# 6ch-dimmer.net
KiCad netlist of a schematic drawn in EAGLE
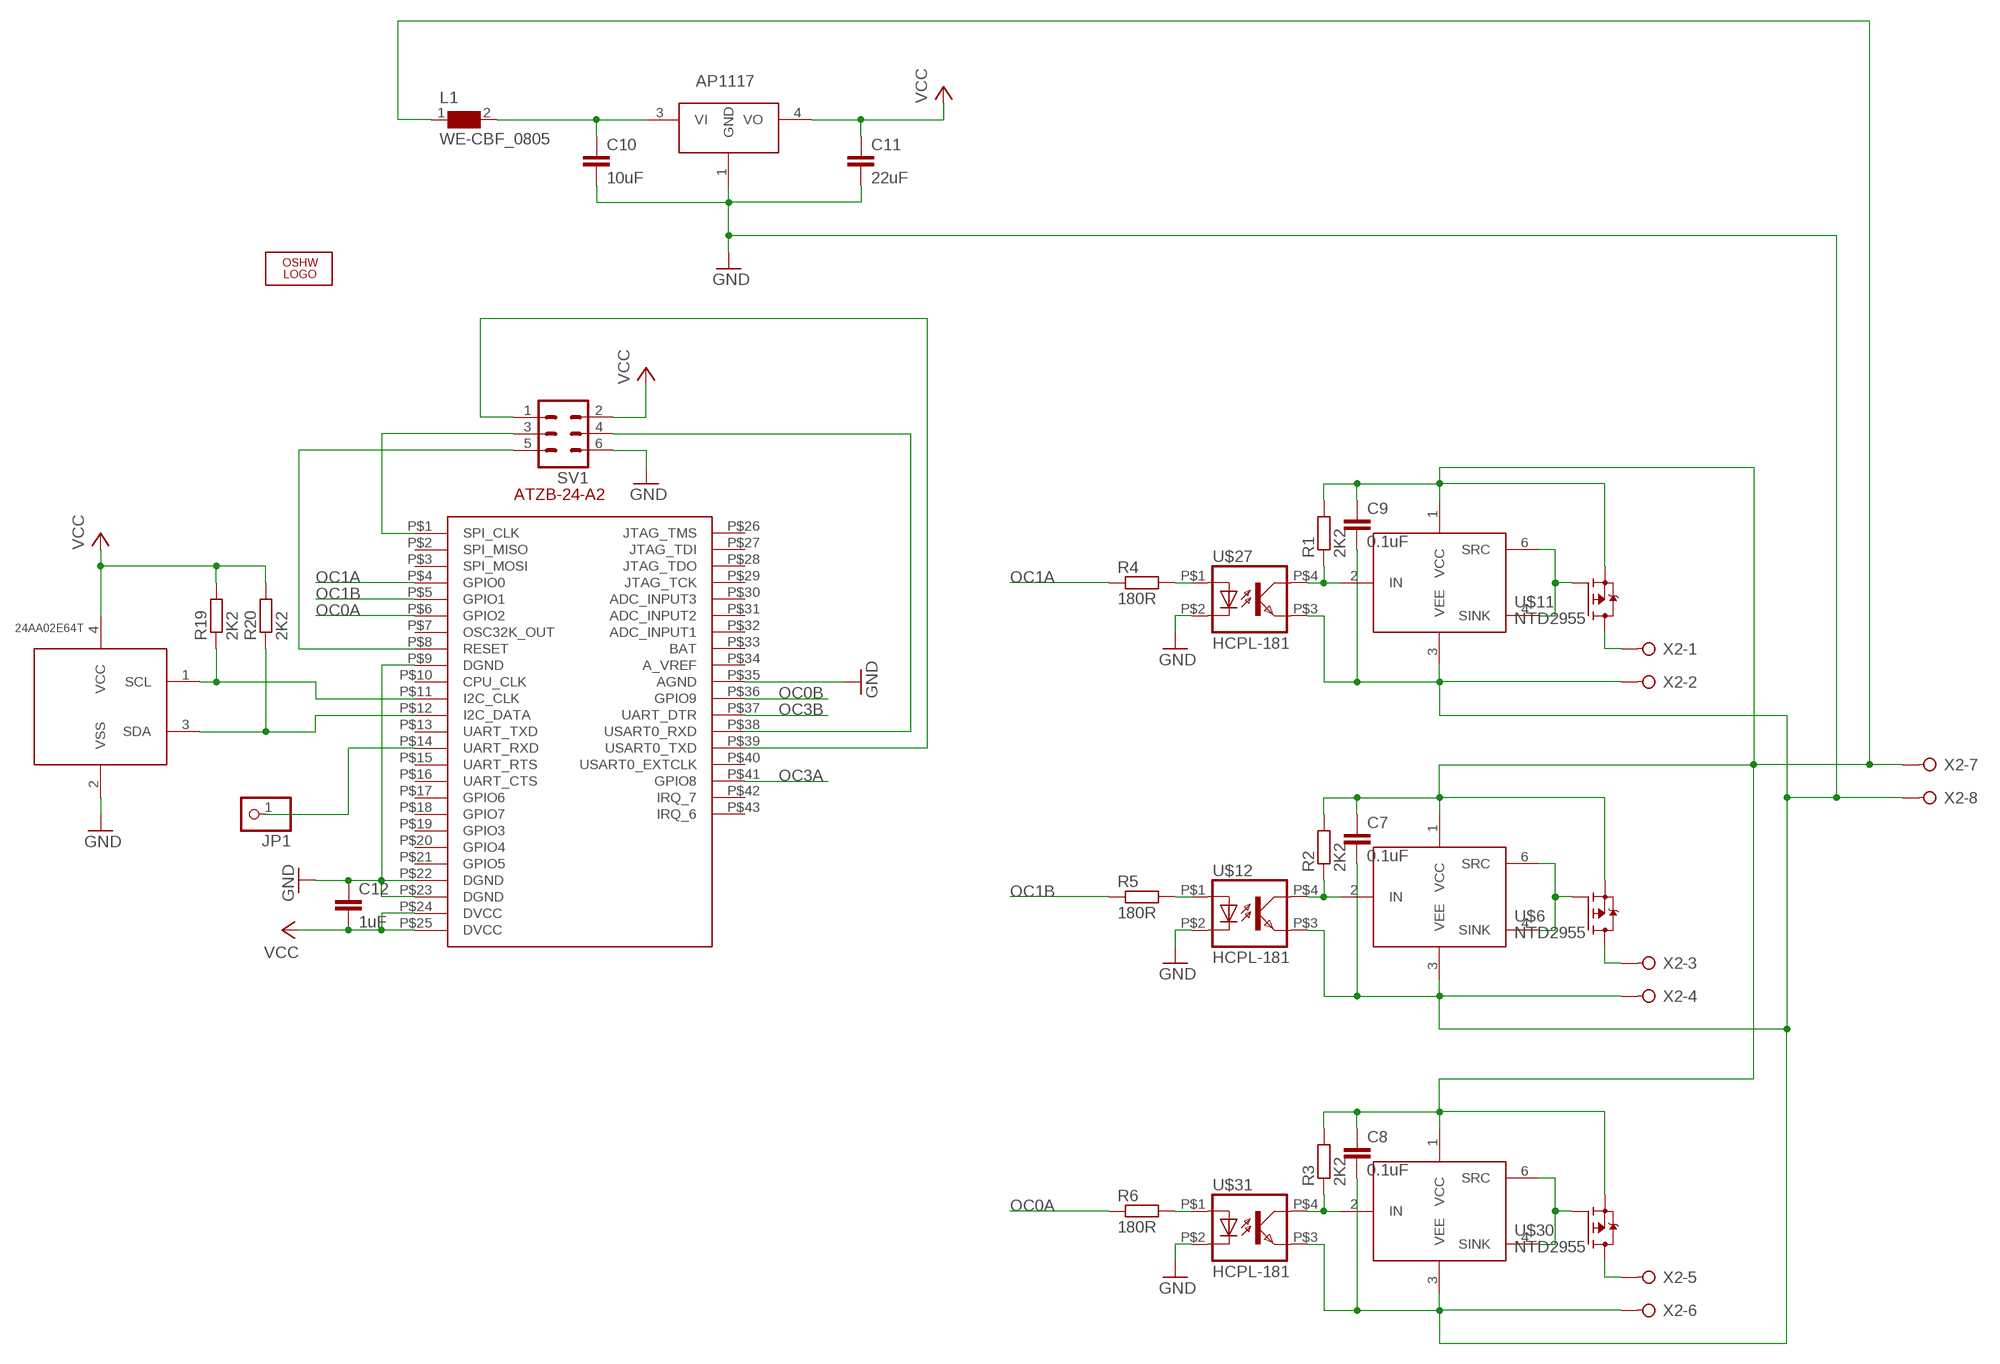
[diagram p0: schematic, sheet 1, part 1 of 2]
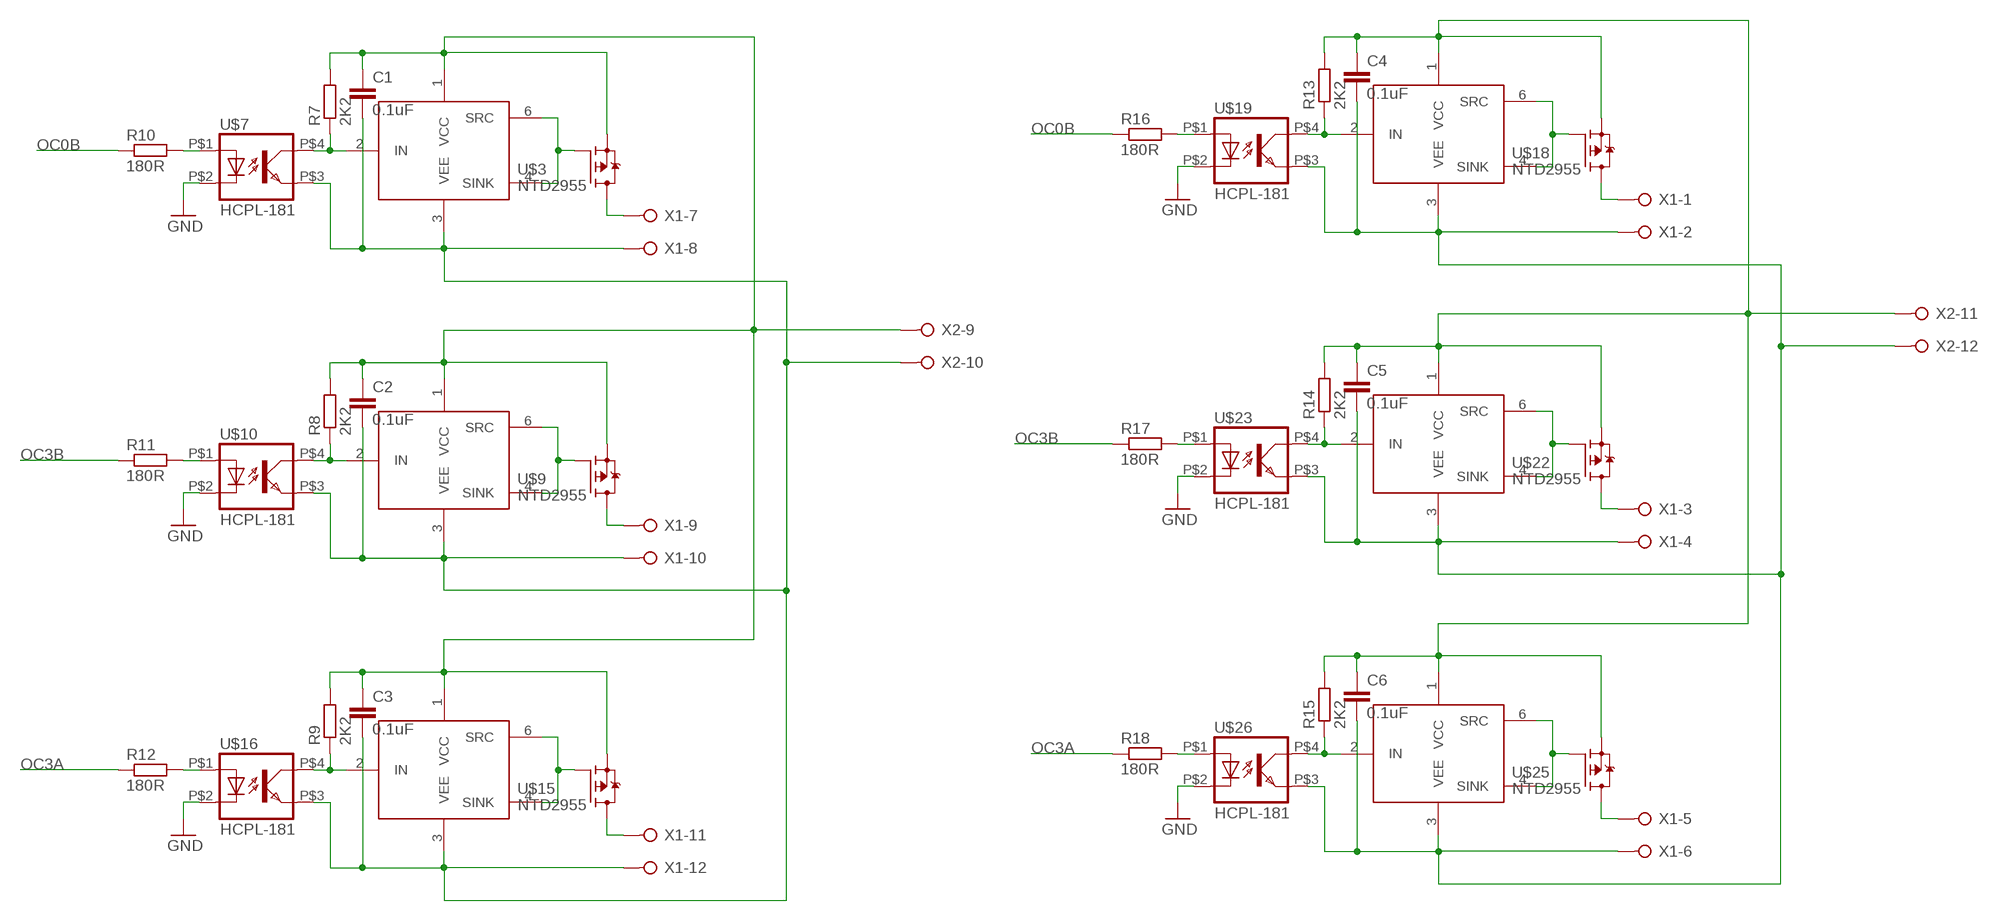
[diagram p1: schematic, sheet 1, part 2 of 2]

(export (version "E")
  (design (tool "Eeschema 10.0.6"))
  (components
    (comp (ref "C1")
      (value "0.1uF")
      (footprint "eagle-import:C0603")
      (libsource (lib "eagle-import") (part "C-EUC0603"))
    )
    (comp (ref "C2")
      (value "0.1uF")
      (footprint "eagle-import:C0603")
      (libsource (lib "eagle-import") (part "C-EUC0603"))
    )
    (comp (ref "C3")
      (value "0.1uF")
      (footprint "eagle-import:C0603")
      (libsource (lib "eagle-import") (part "C-EUC0603"))
    )
    (comp (ref "C4")
      (value "0.1uF")
      (footprint "eagle-import:C0603")
      (libsource (lib "eagle-import") (part "C-EUC0603"))
    )
    (comp (ref "C5")
      (value "0.1uF")
      (footprint "eagle-import:C0603")
      (libsource (lib "eagle-import") (part "C-EUC0603"))
    )
    (comp (ref "C6")
      (value "0.1uF")
      (footprint "eagle-import:C0603")
      (libsource (lib "eagle-import") (part "C-EUC0603"))
    )
    (comp (ref "C7")
      (value "0.1uF")
      (footprint "eagle-import:C0603")
      (libsource (lib "eagle-import") (part "C-EUC0603"))
    )
    (comp (ref "C8")
      (value "0.1uF")
      (footprint "eagle-import:C0603")
      (libsource (lib "eagle-import") (part "C-EUC0603"))
    )
    (comp (ref "C9")
      (value "0.1uF")
      (footprint "eagle-import:C0603")
      (libsource (lib "eagle-import") (part "C-EUC0603"))
    )
    (comp (ref "C10")
      (value "10uF")
      (footprint "eagle-import:C1210")
      (libsource (lib "eagle-import") (part "C-EUC1210"))
    )
    (comp (ref "C11")
      (value "22uF")
      (footprint "eagle-import:C1210")
      (libsource (lib "eagle-import") (part "C-EUC1210"))
    )
    (comp (ref "C12")
      (value "1uF")
      (footprint "eagle-import:C0603")
      (libsource (lib "eagle-import") (part "C-EUC0603"))
    )
    (comp (ref "JP1")
      (value "PINHD-1X1")
      (footprint "eagle-import:1X01")
      (libsource (lib "eagle-import") (part "PINHD-1X1"))
    )
    (comp (ref "L1")
      (value "WE-CBF_0805")
      (footprint "eagle-import:0805")
      (libsource (lib "eagle-import") (part "WE-CBF_0805"))
    )
    (comp (ref "LOGO1")
      (value "OSHW_LOGO_10MILX0500-NT")
      (footprint "eagle-import:OSHW_10X500_NOTEXT")
      (libsource (lib "eagle-import") (part "OSHW_LOGO_10MILX0500-NT"))
    )
    (comp (ref "R1")
      (value "2K2")
      (footprint "eagle-import:R0603")
      (libsource (lib "eagle-import") (part "R-EU_R0603"))
    )
    (comp (ref "R2")
      (value "2K2")
      (footprint "eagle-import:R0603")
      (libsource (lib "eagle-import") (part "R-EU_R0603"))
    )
    (comp (ref "R3")
      (value "2K2")
      (footprint "eagle-import:R0603")
      (libsource (lib "eagle-import") (part "R-EU_R0603"))
    )
    (comp (ref "R4")
      (value "180R")
      (footprint "eagle-import:R0603")
      (libsource (lib "eagle-import") (part "R-EU_R0603"))
    )
    (comp (ref "R5")
      (value "180R")
      (footprint "eagle-import:R0603")
      (libsource (lib "eagle-import") (part "R-EU_R0603"))
    )
    (comp (ref "R6")
      (value "180R")
      (footprint "eagle-import:R0603")
      (libsource (lib "eagle-import") (part "R-EU_R0603"))
    )
    (comp (ref "R7")
      (value "2K2")
      (footprint "eagle-import:R0603")
      (libsource (lib "eagle-import") (part "R-EU_R0603"))
    )
    (comp (ref "R8")
      (value "2K2")
      (footprint "eagle-import:R0603")
      (libsource (lib "eagle-import") (part "R-EU_R0603"))
    )
    (comp (ref "R9")
      (value "2K2")
      (footprint "eagle-import:R0603")
      (libsource (lib "eagle-import") (part "R-EU_R0603"))
    )
    (comp (ref "R10")
      (value "180R")
      (footprint "eagle-import:R0603")
      (libsource (lib "eagle-import") (part "R-EU_R0603"))
    )
    (comp (ref "R11")
      (value "180R")
      (footprint "eagle-import:R0603")
      (libsource (lib "eagle-import") (part "R-EU_R0603"))
    )
    (comp (ref "R12")
      (value "180R")
      (footprint "eagle-import:R0603")
      (libsource (lib "eagle-import") (part "R-EU_R0603"))
    )
    (comp (ref "R13")
      (value "2K2")
      (footprint "eagle-import:R0603")
      (libsource (lib "eagle-import") (part "R-EU_R0603"))
    )
    (comp (ref "R14")
      (value "2K2")
      (footprint "eagle-import:R0603")
      (libsource (lib "eagle-import") (part "R-EU_R0603"))
    )
    (comp (ref "R15")
      (value "2K2")
      (footprint "eagle-import:R0603")
      (libsource (lib "eagle-import") (part "R-EU_R0603"))
    )
    (comp (ref "R16")
      (value "180R")
      (footprint "eagle-import:R0603")
      (libsource (lib "eagle-import") (part "R-EU_R0603"))
    )
    (comp (ref "R17")
      (value "180R")
      (footprint "eagle-import:R0603")
      (libsource (lib "eagle-import") (part "R-EU_R0603"))
    )
    (comp (ref "R18")
      (value "180R")
      (footprint "eagle-import:R0603")
      (libsource (lib "eagle-import") (part "R-EU_R0603"))
    )
    (comp (ref "R19")
      (value "2K2")
      (footprint "eagle-import:R0603")
      (libsource (lib "eagle-import") (part "R-EU_R0603"))
    )
    (comp (ref "R20")
      (value "2K2")
      (footprint "eagle-import:R0603")
      (libsource (lib "eagle-import") (part "R-EU_R0603"))
    )
    (comp (ref "SV1")
      (value "MA03-2")
      (footprint "eagle-import:MA03-2")
      (libsource (lib "eagle-import") (part "MA03-2"))
    )
    (comp (ref "U$1")
      (value "ATZB-24-A2")
      (footprint "eagle-import:ATZB-24-A2")
      (libsource (lib "eagle-import") (part "ATZB-24-A2"))
    )
    (comp (ref "U$2")
      (value "ZXGD3005E6")
      (footprint "eagle-import:SOT23-6")
      (libsource (lib "eagle-import") (part "ZXGD3005E6"))
    )
    (comp (ref "U$3")
      (value "NTD2955")
      (footprint "eagle-import:DPAK")
      (libsource (lib "eagle-import") (part "NTD2955"))
    )
    (comp (ref "U$4")
      (value "ZXGD3005E6")
      (footprint "eagle-import:SOT23-6")
      (libsource (lib "eagle-import") (part "ZXGD3005E6"))
    )
    (comp (ref "U$5")
      (value "ZXGD3005E6")
      (footprint "eagle-import:SOT23-6")
      (libsource (lib "eagle-import") (part "ZXGD3005E6"))
    )
    (comp (ref "U$6")
      (value "NTD2955")
      (footprint "eagle-import:DPAK")
      (libsource (lib "eagle-import") (part "NTD2955"))
    )
    (comp (ref "U$7")
      (value "HCPL-181")
      (footprint "eagle-import:HCPL-181")
      (libsource (lib "eagle-import") (part "HCPL-181"))
    )
    (comp (ref "U$8")
      (value "ZXGD3005E6")
      (footprint "eagle-import:SOT23-6")
      (libsource (lib "eagle-import") (part "ZXGD3005E6"))
    )
    (comp (ref "U$9")
      (value "NTD2955")
      (footprint "eagle-import:DPAK")
      (libsource (lib "eagle-import") (part "NTD2955"))
    )
    (comp (ref "U$10")
      (value "HCPL-181")
      (footprint "eagle-import:HCPL-181")
      (libsource (lib "eagle-import") (part "HCPL-181"))
    )
    (comp (ref "U$11")
      (value "NTD2955")
      (footprint "eagle-import:DPAK")
      (libsource (lib "eagle-import") (part "NTD2955"))
    )
    (comp (ref "U$12")
      (value "HCPL-181")
      (footprint "eagle-import:HCPL-181")
      (libsource (lib "eagle-import") (part "HCPL-181"))
    )
    (comp (ref "U$13")
      (value "ZXGD3005E6")
      (footprint "eagle-import:SOT23-6")
      (libsource (lib "eagle-import") (part "ZXGD3005E6"))
    )
    (comp (ref "U$14")
      (value "ZXGD3005E6")
      (footprint "eagle-import:SOT23-6")
      (libsource (lib "eagle-import") (part "ZXGD3005E6"))
    )
    (comp (ref "U$15")
      (value "NTD2955")
      (footprint "eagle-import:DPAK")
      (libsource (lib "eagle-import") (part "NTD2955"))
    )
    (comp (ref "U$16")
      (value "HCPL-181")
      (footprint "eagle-import:HCPL-181")
      (libsource (lib "eagle-import") (part "HCPL-181"))
    )
    (comp (ref "U$17")
      (value "ZXGD3005E6")
      (footprint "eagle-import:SOT23-6")
      (libsource (lib "eagle-import") (part "ZXGD3005E6"))
    )
    (comp (ref "U$18")
      (value "NTD2955")
      (footprint "eagle-import:DPAK")
      (libsource (lib "eagle-import") (part "NTD2955"))
    )
    (comp (ref "U$19")
      (value "HCPL-181")
      (footprint "eagle-import:HCPL-181")
      (libsource (lib "eagle-import") (part "HCPL-181"))
    )
    (comp (ref "U$20")
      (value "24AA02E64T")
      (footprint "eagle-import:SOT23-5L")
      (libsource (lib "eagle-import") (part "24AA02E64T"))
    )
    (comp (ref "U$21")
      (value "ZXGD3005E6")
      (footprint "eagle-import:SOT23-6")
      (libsource (lib "eagle-import") (part "ZXGD3005E6"))
    )
    (comp (ref "U$22")
      (value "NTD2955")
      (footprint "eagle-import:DPAK")
      (libsource (lib "eagle-import") (part "NTD2955"))
    )
    (comp (ref "U$23")
      (value "HCPL-181")
      (footprint "eagle-import:HCPL-181")
      (libsource (lib "eagle-import") (part "HCPL-181"))
    )
    (comp (ref "U$24")
      (value "ZXGD3005E6")
      (footprint "eagle-import:SOT23-6")
      (libsource (lib "eagle-import") (part "ZXGD3005E6"))
    )
    (comp (ref "U$25")
      (value "NTD2955")
      (footprint "eagle-import:DPAK")
      (libsource (lib "eagle-import") (part "NTD2955"))
    )
    (comp (ref "U$26")
      (value "HCPL-181")
      (footprint "eagle-import:HCPL-181")
      (libsource (lib "eagle-import") (part "HCPL-181"))
    )
    (comp (ref "U$27")
      (value "HCPL-181")
      (footprint "eagle-import:HCPL-181")
      (libsource (lib "eagle-import") (part "HCPL-181"))
    )
    (comp (ref "U$28")
      (value "AP1117")
      (footprint "eagle-import:SOT223")
      (libsource (lib "eagle-import") (part "AP1117"))
    )
    (comp (ref "U$30")
      (value "NTD2955")
      (footprint "eagle-import:DPAK")
      (libsource (lib "eagle-import") (part "NTD2955"))
    )
    (comp (ref "U$31")
      (value "HCPL-181")
      (footprint "eagle-import:HCPL-181")
      (libsource (lib "eagle-import") (part "HCPL-181"))
    )
    (comp (ref "X1")
      (value "W237-12P")
      (footprint "eagle-import:W237-12P")
      (libsource (lib "eagle-import") (part "W237-12P"))
    )
    (comp (ref "X2")
      (value "W237-12P")
      (footprint "eagle-import:W237-12P")
      (libsource (lib "eagle-import") (part "W237-12P"))
    )
  )
  (nets
    (net (code "1") (name "/OC0A") (class "Default")
      (node (ref "R6") (pin "1") (pinfunction "1_1") (pintype "passive"))
      (node (ref "U$1") (pin "P$6") (pinfunction "GPIO2_P$6") (pintype "bidirectional"))
    )
    (net (code "2") (name "/OC0B") (class "Default")
      (node (ref "R10") (pin "1") (pinfunction "1_1") (pintype "passive"))
      (node (ref "R16") (pin "1") (pinfunction "1_1") (pintype "passive"))
      (node (ref "U$1") (pin "P$36") (pinfunction "GPIO9_P$36") (pintype "bidirectional"))
    )
    (net (code "3") (name "/OC1A") (class "Default")
      (node (ref "R4") (pin "1") (pinfunction "1_1") (pintype "passive"))
      (node (ref "U$1") (pin "P$4") (pinfunction "GPIO0_P$4") (pintype "bidirectional"))
    )
    (net (code "4") (name "/OC1B") (class "Default")
      (node (ref "R5") (pin "1") (pinfunction "1_1") (pintype "passive"))
      (node (ref "U$1") (pin "P$5") (pinfunction "GPIO1_P$5") (pintype "bidirectional"))
    )
    (net (code "5") (name "/OC3A") (class "Default")
      (node (ref "R12") (pin "1") (pinfunction "1_1") (pintype "passive"))
      (node (ref "R18") (pin "1") (pinfunction "1_1") (pintype "passive"))
      (node (ref "U$1") (pin "P$41") (pinfunction "GPIO8_P$41") (pintype "bidirectional"))
    )
    (net (code "6") (name "/OC3B") (class "Default")
      (node (ref "R11") (pin "1") (pinfunction "1_1") (pintype "passive"))
      (node (ref "R17") (pin "1") (pinfunction "1_1") (pintype "passive"))
      (node (ref "U$1") (pin "P$37") (pinfunction "UART_DTR_P$37") (pintype "bidirectional"))
    )
    (net (code "7") (name "GND") (class "Default")
      (node (ref "C10") (pin "2") (pinfunction "2_2") (pintype "passive"))
      (node (ref "C11") (pin "2") (pinfunction "2_2") (pintype "passive"))
      (node (ref "C12") (pin "1") (pinfunction "1_1") (pintype "passive"))
      (node (ref "C7") (pin "2") (pinfunction "2_2") (pintype "passive"))
      (node (ref "C8") (pin "2") (pinfunction "2_2") (pintype "passive"))
      (node (ref "C9") (pin "2") (pinfunction "2_2") (pintype "passive"))
      (node (ref "SV1") (pin "6") (pinfunction "6_6") (pintype "passive"))
      (node (ref "U$1") (pin "P$22") (pinfunction "DGND_P$22") (pintype "bidirectional"))
      (node (ref "U$1") (pin "P$23") (pinfunction "DGND_P$23") (pintype "bidirectional"))
      (node (ref "U$1") (pin "P$35") (pinfunction "AGND_P$35") (pintype "bidirectional"))
      (node (ref "U$1") (pin "P$9") (pinfunction "DGND_P$9") (pintype "bidirectional"))
      (node (ref "U$10") (pin "P$2") (pinfunction "C_P$2") (pintype "passive"))
      (node (ref "U$12") (pin "P$2") (pinfunction "C_P$2") (pintype "passive"))
      (node (ref "U$12") (pin "P$3") (pinfunction "EMIT_P$3") (pintype "passive"))
      (node (ref "U$13") (pin "3") (pinfunction "VEE_3") (pintype "bidirectional"))
      (node (ref "U$16") (pin "P$2") (pinfunction "C_P$2") (pintype "passive"))
      (node (ref "U$19") (pin "P$2") (pinfunction "C_P$2") (pintype "passive"))
      (node (ref "U$20") (pin "2") (pinfunction "VSS_2") (pintype "bidirectional"))
      (node (ref "U$23") (pin "P$2") (pinfunction "C_P$2") (pintype "passive"))
      (node (ref "U$26") (pin "P$2") (pinfunction "C_P$2") (pintype "passive"))
      (node (ref "U$27") (pin "P$2") (pinfunction "C_P$2") (pintype "passive"))
      (node (ref "U$27") (pin "P$3") (pinfunction "EMIT_P$3") (pintype "passive"))
      (node (ref "U$28") (pin "1") (pinfunction "GND_1") (pintype "bidirectional"))
      (node (ref "U$31") (pin "P$2") (pinfunction "C_P$2") (pintype "passive"))
      (node (ref "U$31") (pin "P$3") (pinfunction "EMIT_P$3") (pintype "passive"))
      (node (ref "U$4") (pin "3") (pinfunction "VEE_3") (pintype "bidirectional"))
      (node (ref "U$5") (pin "3") (pinfunction "VEE_3") (pintype "bidirectional"))
      (node (ref "U$7") (pin "P$2") (pinfunction "C_P$2") (pintype "passive"))
      (node (ref "X2") (pin "2") (pinfunction "KL_2") (pintype "passive"))
      (node (ref "X2") (pin "4") (pinfunction "KL_4") (pintype "passive"))
      (node (ref "X2") (pin "6") (pinfunction "KL_6") (pintype "passive"))
      (node (ref "X2") (pin "8") (pinfunction "KL_8") (pintype "passive"))
    )
    (net (code "8") (name "Net-(U$1-I2C_CLK)") (class "Default")
      (node (ref "R19") (pin "1") (pinfunction "1_1") (pintype "passive"))
      (node (ref "U$1") (pin "P$11") (pinfunction "I2C_CLK_P$11") (pintype "bidirectional"))
      (node (ref "U$20") (pin "1") (pinfunction "SCL_1") (pintype "bidirectional"))
    )
    (net (code "9") (name "Net-(U$1-I2C_DATA)") (class "Default")
      (node (ref "R20") (pin "1") (pinfunction "1_1") (pintype "passive"))
      (node (ref "U$1") (pin "P$12") (pinfunction "I2C_DATA_P$12") (pintype "bidirectional"))
      (node (ref "U$20") (pin "3") (pinfunction "SDA_3") (pintype "bidirectional"))
    )
    (net (code "10") (name "Net-(U$1-RESET)") (class "Default")
      (node (ref "SV1") (pin "5") (pinfunction "5_5") (pintype "passive"))
      (node (ref "U$1") (pin "P$8") (pinfunction "RESET_P$8") (pintype "bidirectional"))
    )
    (net (code "11") (name "Net-(U$1-SPI_CLK)") (class "Default")
      (node (ref "SV1") (pin "3") (pinfunction "3_3") (pintype "passive"))
      (node (ref "U$1") (pin "P$1") (pinfunction "SPI_CLK_P$1") (pintype "bidirectional"))
    )
    (net (code "12") (name "Net-(U$1-UART_RXD)") (class "Default")
      (node (ref "JP1") (pin "1") (pinfunction "1_1") (pintype "passive"))
      (node (ref "U$1") (pin "P$14") (pinfunction "UART_RXD_P$14") (pintype "bidirectional"))
    )
    (net (code "13") (name "Net-(U$1-USART0_RXD)") (class "Default")
      (node (ref "SV1") (pin "4") (pinfunction "4_4") (pintype "passive"))
      (node (ref "U$1") (pin "P$38") (pinfunction "USART0_RXD_P$38") (pintype "bidirectional"))
    )
    (net (code "14") (name "Net-(U$1-USART0_TXD)") (class "Default")
      (node (ref "SV1") (pin "1") (pinfunction "1_1") (pintype "passive"))
      (node (ref "U$1") (pin "P$39") (pinfunction "USART0_TXD_P$39") (pintype "bidirectional"))
    )
    (net (code "15") (name "Net-(U$2-IN)") (class "Default")
      (node (ref "R7") (pin "1") (pinfunction "1_1") (pintype "passive"))
      (node (ref "U$2") (pin "2") (pinfunction "IN_2") (pintype "bidirectional"))
      (node (ref "U$7") (pin "P$4") (pinfunction "COL_P$4") (pintype "passive"))
    )
    (net (code "16") (name "Net-(U$2-SINK)") (class "Default")
      (node (ref "U$2") (pin "4") (pinfunction "SINK_4") (pintype "bidirectional"))
      (node (ref "U$2") (pin "6") (pinfunction "SRC_6") (pintype "bidirectional"))
      (node (ref "U$3") (pin "1") (pinfunction "G_1") (pintype "passive"))
    )
    (net (code "17") (name "Net-(U$3-D)") (class "Default")
      (node (ref "U$3") (pin "4") (pinfunction "D_4") (pintype "passive"))
      (node (ref "X1") (pin "7") (pinfunction "KL_7") (pintype "passive"))
    )
    (net (code "18") (name "Net-(U$5-SINK)") (class "Default")
      (node (ref "U$5") (pin "4") (pinfunction "SINK_4") (pintype "bidirectional"))
      (node (ref "U$5") (pin "6") (pinfunction "SRC_6") (pintype "bidirectional"))
      (node (ref "U$6") (pin "1") (pinfunction "G_1") (pintype "passive"))
    )
    (net (code "19") (name "Net-(U$6-D)") (class "Default")
      (node (ref "U$6") (pin "4") (pinfunction "D_4") (pintype "passive"))
      (node (ref "X2") (pin "3") (pinfunction "KL_3") (pintype "passive"))
    )
    (net (code "20") (name "Net-(U$7-A)") (class "Default")
      (node (ref "R10") (pin "2") (pinfunction "2_2") (pintype "passive"))
      (node (ref "U$7") (pin "P$1") (pinfunction "A_P$1") (pintype "passive"))
    )
    (net (code "21") (name "Net-(U$8-SINK)") (class "Default")
      (node (ref "U$8") (pin "4") (pinfunction "SINK_4") (pintype "bidirectional"))
      (node (ref "U$8") (pin "6") (pinfunction "SRC_6") (pintype "bidirectional"))
      (node (ref "U$9") (pin "1") (pinfunction "G_1") (pintype "passive"))
    )
    (net (code "22") (name "Net-(U$9-D)") (class "Default")
      (node (ref "U$9") (pin "4") (pinfunction "D_4") (pintype "passive"))
      (node (ref "X1") (pin "9") (pinfunction "KL_9") (pintype "passive"))
    )
    (net (code "23") (name "Net-(U$10-A)") (class "Default")
      (node (ref "R11") (pin "2") (pinfunction "2_2") (pintype "passive"))
      (node (ref "U$10") (pin "P$1") (pinfunction "A_P$1") (pintype "passive"))
    )
    (net (code "24") (name "Net-(U$10-COL)") (class "Default")
      (node (ref "R8") (pin "1") (pinfunction "1_1") (pintype "passive"))
      (node (ref "U$10") (pin "P$4") (pinfunction "COL_P$4") (pintype "passive"))
      (node (ref "U$8") (pin "2") (pinfunction "IN_2") (pintype "bidirectional"))
    )
    (net (code "25") (name "Net-(U$10-EMIT)") (class "Default")
      (node (ref "C1") (pin "2") (pinfunction "2_2") (pintype "passive"))
      (node (ref "C2") (pin "2") (pinfunction "2_2") (pintype "passive"))
      (node (ref "C3") (pin "2") (pinfunction "2_2") (pintype "passive"))
      (node (ref "U$10") (pin "P$3") (pinfunction "EMIT_P$3") (pintype "passive"))
      (node (ref "U$14") (pin "3") (pinfunction "VEE_3") (pintype "bidirectional"))
      (node (ref "U$16") (pin "P$3") (pinfunction "EMIT_P$3") (pintype "passive"))
      (node (ref "U$2") (pin "3") (pinfunction "VEE_3") (pintype "bidirectional"))
      (node (ref "U$7") (pin "P$3") (pinfunction "EMIT_P$3") (pintype "passive"))
      (node (ref "U$8") (pin "3") (pinfunction "VEE_3") (pintype "bidirectional"))
      (node (ref "X1") (pin "10") (pinfunction "KL_10") (pintype "passive"))
      (node (ref "X1") (pin "12") (pinfunction "KL_12") (pintype "passive"))
      (node (ref "X1") (pin "8") (pinfunction "KL_8") (pintype "passive"))
      (node (ref "X2") (pin "10") (pinfunction "KL_10") (pintype "passive"))
    )
    (net (code "26") (name "Net-(U$11-D)") (class "Default")
      (node (ref "U$11") (pin "4") (pinfunction "D_4") (pintype "passive"))
      (node (ref "X2") (pin "1") (pinfunction "KL_1") (pintype "passive"))
    )
    (net (code "27") (name "Net-(U$11-G)") (class "Default")
      (node (ref "U$11") (pin "1") (pinfunction "G_1") (pintype "passive"))
      (node (ref "U$4") (pin "4") (pinfunction "SINK_4") (pintype "bidirectional"))
      (node (ref "U$4") (pin "6") (pinfunction "SRC_6") (pintype "bidirectional"))
    )
    (net (code "28") (name "Net-(U$11-S)") (class "Default")
      (node (ref "C7") (pin "1") (pinfunction "1_1") (pintype "passive"))
      (node (ref "C8") (pin "1") (pinfunction "1_1") (pintype "passive"))
      (node (ref "C9") (pin "1") (pinfunction "1_1") (pintype "passive"))
      (node (ref "L1") (pin "1") (pinfunction "1_1") (pintype "passive"))
      (node (ref "R1") (pin "2") (pinfunction "2_2") (pintype "passive"))
      (node (ref "R2") (pin "2") (pinfunction "2_2") (pintype "passive"))
      (node (ref "R3") (pin "2") (pinfunction "2_2") (pintype "passive"))
      (node (ref "U$11") (pin "3") (pinfunction "S_3") (pintype "passive"))
      (node (ref "U$13") (pin "1") (pinfunction "VCC_1") (pintype "bidirectional"))
      (node (ref "U$30") (pin "3") (pinfunction "S_3") (pintype "passive"))
      (node (ref "U$4") (pin "1") (pinfunction "VCC_1") (pintype "bidirectional"))
      (node (ref "U$5") (pin "1") (pinfunction "VCC_1") (pintype "bidirectional"))
      (node (ref "U$6") (pin "3") (pinfunction "S_3") (pintype "passive"))
      (node (ref "X2") (pin "7") (pinfunction "KL_7") (pintype "passive"))
    )
    (net (code "29") (name "Net-(U$12-A)") (class "Default")
      (node (ref "R5") (pin "2") (pinfunction "2_2") (pintype "passive"))
      (node (ref "U$12") (pin "P$1") (pinfunction "A_P$1") (pintype "passive"))
    )
    (net (code "30") (name "Net-(U$12-COL)") (class "Default")
      (node (ref "R2") (pin "1") (pinfunction "1_1") (pintype "passive"))
      (node (ref "U$12") (pin "P$4") (pinfunction "COL_P$4") (pintype "passive"))
      (node (ref "U$5") (pin "2") (pinfunction "IN_2") (pintype "bidirectional"))
    )
    (net (code "31") (name "Net-(U$13-IN)") (class "Default")
      (node (ref "R3") (pin "1") (pinfunction "1_1") (pintype "passive"))
      (node (ref "U$13") (pin "2") (pinfunction "IN_2") (pintype "bidirectional"))
      (node (ref "U$31") (pin "P$4") (pinfunction "COL_P$4") (pintype "passive"))
    )
    (net (code "32") (name "Net-(U$13-SINK)") (class "Default")
      (node (ref "U$13") (pin "4") (pinfunction "SINK_4") (pintype "bidirectional"))
      (node (ref "U$13") (pin "6") (pinfunction "SRC_6") (pintype "bidirectional"))
      (node (ref "U$30") (pin "1") (pinfunction "G_1") (pintype "passive"))
    )
    (net (code "33") (name "Net-(U$14-IN)") (class "Default")
      (node (ref "R9") (pin "1") (pinfunction "1_1") (pintype "passive"))
      (node (ref "U$14") (pin "2") (pinfunction "IN_2") (pintype "bidirectional"))
      (node (ref "U$16") (pin "P$4") (pinfunction "COL_P$4") (pintype "passive"))
    )
    (net (code "34") (name "Net-(U$14-SINK)") (class "Default")
      (node (ref "U$14") (pin "4") (pinfunction "SINK_4") (pintype "bidirectional"))
      (node (ref "U$14") (pin "6") (pinfunction "SRC_6") (pintype "bidirectional"))
      (node (ref "U$15") (pin "1") (pinfunction "G_1") (pintype "passive"))
    )
    (net (code "35") (name "Net-(U$14-VCC)") (class "Default")
      (node (ref "C1") (pin "1") (pinfunction "1_1") (pintype "passive"))
      (node (ref "C2") (pin "1") (pinfunction "1_1") (pintype "passive"))
      (node (ref "C3") (pin "1") (pinfunction "1_1") (pintype "passive"))
      (node (ref "R7") (pin "2") (pinfunction "2_2") (pintype "passive"))
      (node (ref "R8") (pin "2") (pinfunction "2_2") (pintype "passive"))
      (node (ref "R9") (pin "2") (pinfunction "2_2") (pintype "passive"))
      (node (ref "U$14") (pin "1") (pinfunction "VCC_1") (pintype "bidirectional"))
      (node (ref "U$15") (pin "3") (pinfunction "S_3") (pintype "passive"))
      (node (ref "U$2") (pin "1") (pinfunction "VCC_1") (pintype "bidirectional"))
      (node (ref "U$3") (pin "3") (pinfunction "S_3") (pintype "passive"))
      (node (ref "U$8") (pin "1") (pinfunction "VCC_1") (pintype "bidirectional"))
      (node (ref "U$9") (pin "3") (pinfunction "S_3") (pintype "passive"))
      (node (ref "X2") (pin "9") (pinfunction "KL_9") (pintype "passive"))
    )
    (net (code "36") (name "Net-(U$15-D)") (class "Default")
      (node (ref "U$15") (pin "4") (pinfunction "D_4") (pintype "passive"))
      (node (ref "X1") (pin "11") (pinfunction "KL_11") (pintype "passive"))
    )
    (net (code "37") (name "Net-(U$16-A)") (class "Default")
      (node (ref "R12") (pin "2") (pinfunction "2_2") (pintype "passive"))
      (node (ref "U$16") (pin "P$1") (pinfunction "A_P$1") (pintype "passive"))
    )
    (net (code "38") (name "Net-(U$17-IN)") (class "Default")
      (node (ref "R13") (pin "1") (pinfunction "1_1") (pintype "passive"))
      (node (ref "U$17") (pin "2") (pinfunction "IN_2") (pintype "bidirectional"))
      (node (ref "U$19") (pin "P$4") (pinfunction "COL_P$4") (pintype "passive"))
    )
    (net (code "39") (name "Net-(U$17-SINK)") (class "Default")
      (node (ref "U$17") (pin "4") (pinfunction "SINK_4") (pintype "bidirectional"))
      (node (ref "U$17") (pin "6") (pinfunction "SRC_6") (pintype "bidirectional"))
      (node (ref "U$18") (pin "1") (pinfunction "G_1") (pintype "passive"))
    )
    (net (code "40") (name "Net-(U$17-VCC)") (class "Default")
      (node (ref "C4") (pin "1") (pinfunction "1_1") (pintype "passive"))
      (node (ref "C5") (pin "1") (pinfunction "1_1") (pintype "passive"))
      (node (ref "C6") (pin "1") (pinfunction "1_1") (pintype "passive"))
      (node (ref "R13") (pin "2") (pinfunction "2_2") (pintype "passive"))
      (node (ref "R14") (pin "2") (pinfunction "2_2") (pintype "passive"))
      (node (ref "R15") (pin "2") (pinfunction "2_2") (pintype "passive"))
      (node (ref "U$17") (pin "1") (pinfunction "VCC_1") (pintype "bidirectional"))
      (node (ref "U$18") (pin "3") (pinfunction "S_3") (pintype "passive"))
      (node (ref "U$21") (pin "1") (pinfunction "VCC_1") (pintype "bidirectional"))
      (node (ref "U$22") (pin "3") (pinfunction "S_3") (pintype "passive"))
      (node (ref "U$24") (pin "1") (pinfunction "VCC_1") (pintype "bidirectional"))
      (node (ref "U$25") (pin "3") (pinfunction "S_3") (pintype "passive"))
      (node (ref "X2") (pin "11") (pinfunction "KL_11") (pintype "passive"))
    )
    (net (code "41") (name "Net-(U$17-VEE)") (class "Default")
      (node (ref "C4") (pin "2") (pinfunction "2_2") (pintype "passive"))
      (node (ref "C5") (pin "2") (pinfunction "2_2") (pintype "passive"))
      (node (ref "C6") (pin "2") (pinfunction "2_2") (pintype "passive"))
      (node (ref "U$17") (pin "3") (pinfunction "VEE_3") (pintype "bidirectional"))
      (node (ref "U$19") (pin "P$3") (pinfunction "EMIT_P$3") (pintype "passive"))
      (node (ref "U$21") (pin "3") (pinfunction "VEE_3") (pintype "bidirectional"))
      (node (ref "U$23") (pin "P$3") (pinfunction "EMIT_P$3") (pintype "passive"))
      (node (ref "U$24") (pin "3") (pinfunction "VEE_3") (pintype "bidirectional"))
      (node (ref "U$26") (pin "P$3") (pinfunction "EMIT_P$3") (pintype "passive"))
      (node (ref "X1") (pin "2") (pinfunction "KL_2") (pintype "passive"))
      (node (ref "X1") (pin "4") (pinfunction "KL_4") (pintype "passive"))
      (node (ref "X1") (pin "6") (pinfunction "KL_6") (pintype "passive"))
      (node (ref "X2") (pin "12") (pinfunction "KL_12") (pintype "passive"))
    )
    (net (code "42") (name "Net-(U$18-D)") (class "Default")
      (node (ref "U$18") (pin "4") (pinfunction "D_4") (pintype "passive"))
      (node (ref "X1") (pin "1") (pinfunction "KL_1") (pintype "passive"))
    )
    (net (code "43") (name "Net-(U$19-A)") (class "Default")
      (node (ref "R16") (pin "2") (pinfunction "2_2") (pintype "passive"))
      (node (ref "U$19") (pin "P$1") (pinfunction "A_P$1") (pintype "passive"))
    )
    (net (code "44") (name "Net-(U$21-IN)") (class "Default")
      (node (ref "R14") (pin "1") (pinfunction "1_1") (pintype "passive"))
      (node (ref "U$21") (pin "2") (pinfunction "IN_2") (pintype "bidirectional"))
      (node (ref "U$23") (pin "P$4") (pinfunction "COL_P$4") (pintype "passive"))
    )
    (net (code "45") (name "Net-(U$21-SINK)") (class "Default")
      (node (ref "U$21") (pin "4") (pinfunction "SINK_4") (pintype "bidirectional"))
      (node (ref "U$21") (pin "6") (pinfunction "SRC_6") (pintype "bidirectional"))
      (node (ref "U$22") (pin "1") (pinfunction "G_1") (pintype "passive"))
    )
    (net (code "46") (name "Net-(U$22-D)") (class "Default")
      (node (ref "U$22") (pin "4") (pinfunction "D_4") (pintype "passive"))
      (node (ref "X1") (pin "3") (pinfunction "KL_3") (pintype "passive"))
    )
    (net (code "47") (name "Net-(U$23-A)") (class "Default")
      (node (ref "R17") (pin "2") (pinfunction "2_2") (pintype "passive"))
      (node (ref "U$23") (pin "P$1") (pinfunction "A_P$1") (pintype "passive"))
    )
    (net (code "48") (name "Net-(U$24-IN)") (class "Default")
      (node (ref "R15") (pin "1") (pinfunction "1_1") (pintype "passive"))
      (node (ref "U$24") (pin "2") (pinfunction "IN_2") (pintype "bidirectional"))
      (node (ref "U$26") (pin "P$4") (pinfunction "COL_P$4") (pintype "passive"))
    )
    (net (code "49") (name "Net-(U$24-SINK)") (class "Default")
      (node (ref "U$24") (pin "4") (pinfunction "SINK_4") (pintype "bidirectional"))
      (node (ref "U$24") (pin "6") (pinfunction "SRC_6") (pintype "bidirectional"))
      (node (ref "U$25") (pin "1") (pinfunction "G_1") (pintype "passive"))
    )
    (net (code "50") (name "Net-(U$25-D)") (class "Default")
      (node (ref "U$25") (pin "4") (pinfunction "D_4") (pintype "passive"))
      (node (ref "X1") (pin "5") (pinfunction "KL_5") (pintype "passive"))
    )
    (net (code "51") (name "Net-(U$26-A)") (class "Default")
      (node (ref "R18") (pin "2") (pinfunction "2_2") (pintype "passive"))
      (node (ref "U$26") (pin "P$1") (pinfunction "A_P$1") (pintype "passive"))
    )
    (net (code "52") (name "Net-(U$27-A)") (class "Default")
      (node (ref "R4") (pin "2") (pinfunction "2_2") (pintype "passive"))
      (node (ref "U$27") (pin "P$1") (pinfunction "A_P$1") (pintype "passive"))
    )
    (net (code "53") (name "Net-(U$27-COL)") (class "Default")
      (node (ref "R1") (pin "1") (pinfunction "1_1") (pintype "passive"))
      (node (ref "U$27") (pin "P$4") (pinfunction "COL_P$4") (pintype "passive"))
      (node (ref "U$4") (pin "2") (pinfunction "IN_2") (pintype "bidirectional"))
    )
    (net (code "54") (name "Net-(U$28-VI)") (class "Default")
      (node (ref "C10") (pin "1") (pinfunction "1_1") (pintype "passive"))
      (node (ref "L1") (pin "2") (pinfunction "2_2") (pintype "passive"))
      (node (ref "U$28") (pin "3") (pinfunction "VI_3") (pintype "bidirectional"))
    )
    (net (code "55") (name "Net-(U$30-D)") (class "Default")
      (node (ref "U$30") (pin "4") (pinfunction "D_4") (pintype "passive"))
      (node (ref "X2") (pin "5") (pinfunction "KL_5") (pintype "passive"))
    )
    (net (code "56") (name "Net-(U$31-A)") (class "Default")
      (node (ref "R6") (pin "2") (pinfunction "2_2") (pintype "passive"))
      (node (ref "U$31") (pin "P$1") (pinfunction "A_P$1") (pintype "passive"))
    )
    (net (code "57") (name "VCC") (class "Default")
      (node (ref "C11") (pin "1") (pinfunction "1_1") (pintype "passive"))
      (node (ref "C12") (pin "2") (pinfunction "2_2") (pintype "passive"))
      (node (ref "R19") (pin "2") (pinfunction "2_2") (pintype "passive"))
      (node (ref "R20") (pin "2") (pinfunction "2_2") (pintype "passive"))
      (node (ref "SV1") (pin "2") (pinfunction "2_2") (pintype "passive"))
      (node (ref "U$1") (pin "P$24") (pinfunction "DVCC_P$24") (pintype "bidirectional"))
      (node (ref "U$1") (pin "P$25") (pinfunction "DVCC_P$25") (pintype "bidirectional"))
      (node (ref "U$20") (pin "4") (pinfunction "VCC_4") (pintype "bidirectional"))
      (node (ref "U$28") (pin "4") (pinfunction "VO_4") (pintype "bidirectional"))
    )
    (net (code "58") (name "unconnected-(U$1-ADC_INPUT1-PadP$32)") (class "Default")
      (node (ref "U$1") (pin "P$32") (pinfunction "ADC_INPUT1_P$32") (pintype "bidirectional"))
    )
    (net (code "59") (name "unconnected-(U$1-ADC_INPUT2-PadP$31)") (class "Default")
      (node (ref "U$1") (pin "P$31") (pinfunction "ADC_INPUT2_P$31") (pintype "bidirectional"))
    )
    (net (code "60") (name "unconnected-(U$1-ADC_INPUT3-PadP$30)") (class "Default")
      (node (ref "U$1") (pin "P$30") (pinfunction "ADC_INPUT3_P$30") (pintype "bidirectional"))
    )
    (net (code "61") (name "unconnected-(U$1-A_VREF-PadP$34)") (class "Default")
      (node (ref "U$1") (pin "P$34") (pinfunction "A_VREF_P$34") (pintype "bidirectional"))
    )
    (net (code "62") (name "unconnected-(U$1-BAT-PadP$33)") (class "Default")
      (node (ref "U$1") (pin "P$33") (pinfunction "BAT_P$33") (pintype "bidirectional"))
    )
    (net (code "63") (name "unconnected-(U$1-CPU_CLK-PadP$10)") (class "Default")
      (node (ref "U$1") (pin "P$10") (pinfunction "CPU_CLK_P$10") (pintype "bidirectional"))
    )
    (net (code "64") (name "unconnected-(U$1-GPIO3-PadP$19)") (class "Default")
      (node (ref "U$1") (pin "P$19") (pinfunction "GPIO3_P$19") (pintype "bidirectional"))
    )
    (net (code "65") (name "unconnected-(U$1-GPIO4-PadP$20)") (class "Default")
      (node (ref "U$1") (pin "P$20") (pinfunction "GPIO4_P$20") (pintype "bidirectional"))
    )
    (net (code "66") (name "unconnected-(U$1-GPIO5-PadP$21)") (class "Default")
      (node (ref "U$1") (pin "P$21") (pinfunction "GPIO5_P$21") (pintype "bidirectional"))
    )
    (net (code "67") (name "unconnected-(U$1-GPIO6-PadP$17)") (class "Default")
      (node (ref "U$1") (pin "P$17") (pinfunction "GPIO6_P$17") (pintype "bidirectional"))
    )
    (net (code "68") (name "unconnected-(U$1-GPIO7-PadP$18)") (class "Default")
      (node (ref "U$1") (pin "P$18") (pinfunction "GPIO7_P$18") (pintype "bidirectional"))
    )
    (net (code "69") (name "unconnected-(U$1-IRQ_6-PadP$43)") (class "Default")
      (node (ref "U$1") (pin "P$43") (pinfunction "IRQ_6_P$43") (pintype "bidirectional"))
    )
    (net (code "70") (name "unconnected-(U$1-IRQ_7-PadP$42)") (class "Default")
      (node (ref "U$1") (pin "P$42") (pinfunction "IRQ_7_P$42") (pintype "bidirectional"))
    )
    (net (code "71") (name "unconnected-(U$1-JTAG_TCK-PadP$29)") (class "Default")
      (node (ref "U$1") (pin "P$29") (pinfunction "JTAG_TCK_P$29") (pintype "bidirectional"))
    )
    (net (code "72") (name "unconnected-(U$1-JTAG_TDI-PadP$27)") (class "Default")
      (node (ref "U$1") (pin "P$27") (pinfunction "JTAG_TDI_P$27") (pintype "bidirectional"))
    )
    (net (code "73") (name "unconnected-(U$1-JTAG_TDO-PadP$28)") (class "Default")
      (node (ref "U$1") (pin "P$28") (pinfunction "JTAG_TDO_P$28") (pintype "bidirectional"))
    )
    (net (code "74") (name "unconnected-(U$1-JTAG_TMS-PadP$26)") (class "Default")
      (node (ref "U$1") (pin "P$26") (pinfunction "JTAG_TMS_P$26") (pintype "bidirectional"))
    )
    (net (code "75") (name "unconnected-(U$1-OSC32K_OUT-PadP$7)") (class "Default")
      (node (ref "U$1") (pin "P$7") (pinfunction "OSC32K_OUT_P$7") (pintype "bidirectional"))
    )
    (net (code "76") (name "unconnected-(U$1-SPI_MISO-PadP$2)") (class "Default")
      (node (ref "U$1") (pin "P$2") (pinfunction "SPI_MISO_P$2") (pintype "bidirectional"))
    )
    (net (code "77") (name "unconnected-(U$1-SPI_MOSI-PadP$3)") (class "Default")
      (node (ref "U$1") (pin "P$3") (pinfunction "SPI_MOSI_P$3") (pintype "bidirectional"))
    )
    (net (code "78") (name "unconnected-(U$1-UART_CTS-PadP$16)") (class "Default")
      (node (ref "U$1") (pin "P$16") (pinfunction "UART_CTS_P$16") (pintype "bidirectional"))
    )
    (net (code "79") (name "unconnected-(U$1-UART_RTS-PadP$15)") (class "Default")
      (node (ref "U$1") (pin "P$15") (pinfunction "UART_RTS_P$15") (pintype "bidirectional"))
    )
    (net (code "80") (name "unconnected-(U$1-UART_TXD-PadP$13)") (class "Default")
      (node (ref "U$1") (pin "P$13") (pinfunction "UART_TXD_P$13") (pintype "bidirectional"))
    )
    (net (code "81") (name "unconnected-(U$1-USART0_EXTCLK-PadP$40)") (class "Default")
      (node (ref "U$1") (pin "P$40") (pinfunction "USART0_EXTCLK_P$40") (pintype "bidirectional"))
    )
  )
)
